# CH340G_VCC.net
KiCad netlist of a schematic drawn in Altium Designer
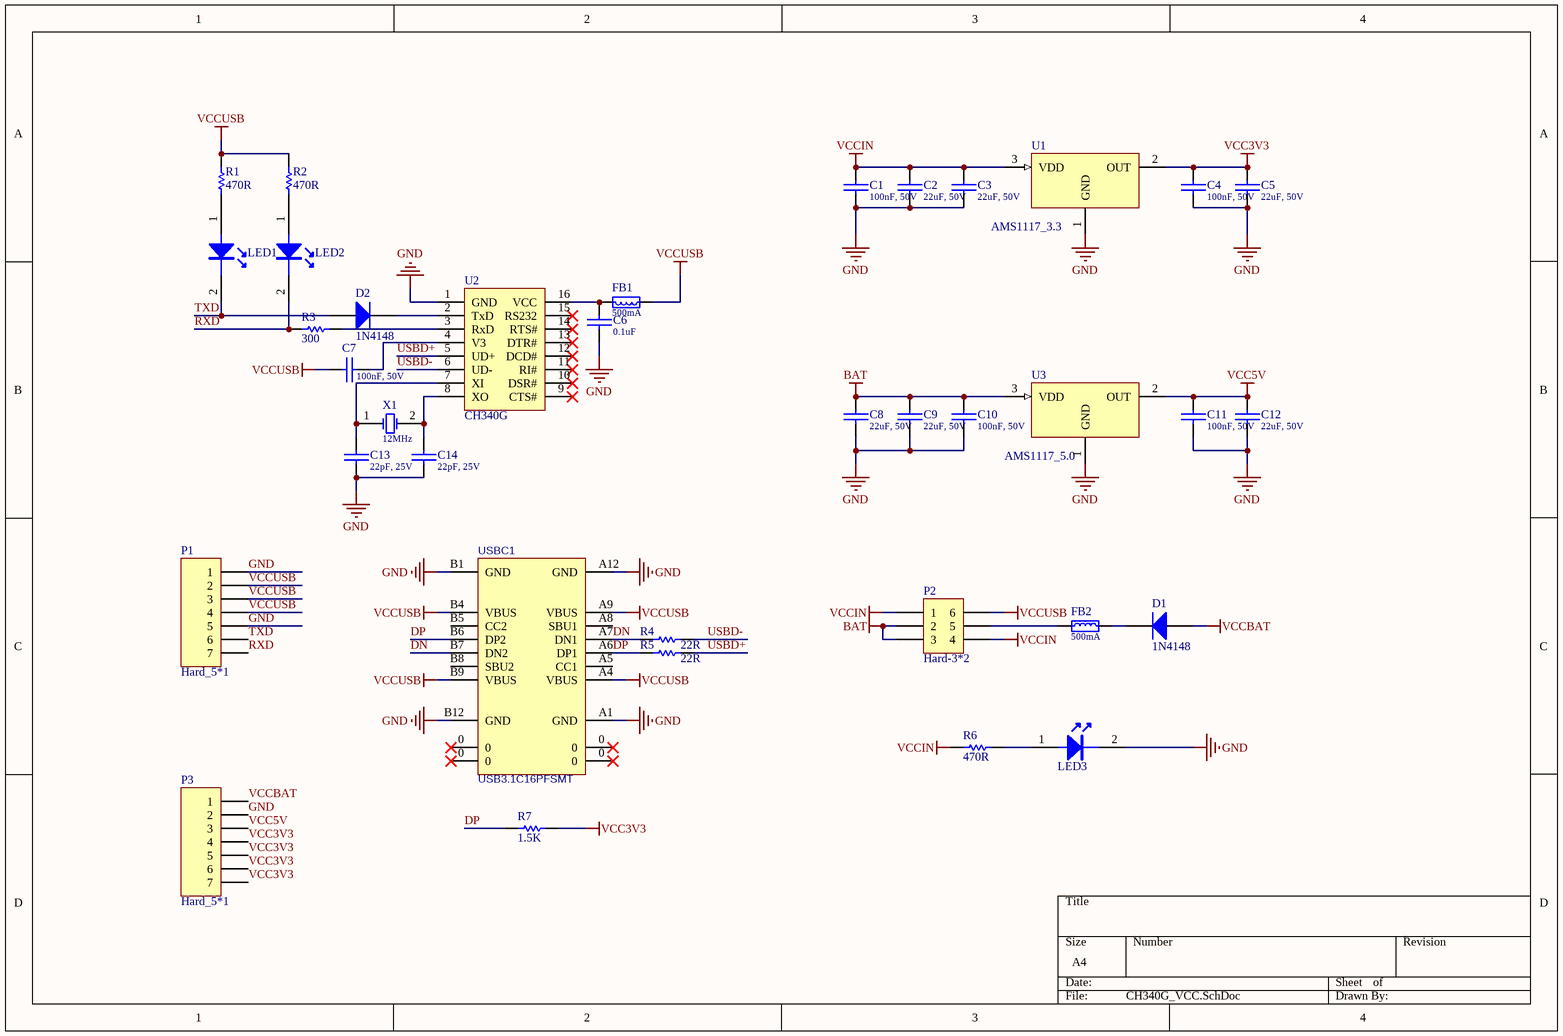
[diagram p0: CH340G_VCC.SchDoc]

(export (version "E")
  (design (tool "Eeschema 10.0.6"))
  (components
    (comp (ref "C1")
      (value "100nF, 50V")
      (footprint "C0603_QB")
      (description "Capacitor")
      (fields (field (name "MANUFACTURER") "国巨") (field (name "PARTNO") "11002050002"))
      (libsource (lib "Schlib1") (part "CAP"))
    )
    (comp (ref "C2")
      (value "22uF, 50V")
      (footprint "C0805_1.25mm_QB")
      (description "Capacitor")
      (fields (field (name "MANUFACTURER") "国巨") (field (name "PARTNO") "11002050002"))
      (libsource (lib "Schlib1") (part "CAP"))
    )
    (comp (ref "C3")
      (value "22uF, 50V")
      (footprint "C0805_1.25mm_QB")
      (description "Capacitor")
      (fields (field (name "MANUFACTURER") "国巨") (field (name "PARTNO") "11002050002"))
      (libsource (lib "Schlib1") (part "CAP"))
    )
    (comp (ref "C4")
      (value "100nF, 50V")
      (footprint "C0603_QB")
      (description "Capacitor")
      (fields (field (name "MANUFACTURER") "国巨") (field (name "PARTNO") "11002050002"))
      (libsource (lib "Schlib1") (part "CAP"))
    )
    (comp (ref "C5")
      (value "22uF, 50V")
      (footprint "C0805_1.25mm_QB")
      (description "Capacitor")
      (fields (field (name "MANUFACTURER") "国巨") (field (name "PARTNO") "11002050002"))
      (libsource (lib "Schlib1") (part "CAP"))
    )
    (comp (ref "C6")
      (value "0.1uF")
      (footprint "C0603_QB")
      (description "Capacitor")
      (fields (field (name "MANUFACTURER") "国巨") (field (name "PARTNO") "11002050002"))
      (libsource (lib "Schlib1") (part "CAP"))
    )
    (comp (ref "C7")
      (value "100nF, 50V")
      (footprint "C0603_QB")
      (description "Capacitor")
      (fields (field (name "MANUFACTURER") "国巨") (field (name "PARTNO") "11002050002"))
      (libsource (lib "Schlib1") (part "CAP"))
    )
    (comp (ref "C8")
      (value "22uF, 50V")
      (footprint "C0805_1.25mm_QB")
      (description "Capacitor")
      (fields (field (name "MANUFACTURER") "国巨") (field (name "PARTNO") "11002050002"))
      (libsource (lib "Schlib1") (part "CAP"))
    )
    (comp (ref "C9")
      (value "22uF, 50V")
      (footprint "C0805_1.25mm_QB")
      (description "Capacitor")
      (fields (field (name "MANUFACTURER") "国巨") (field (name "PARTNO") "11002050002"))
      (libsource (lib "Schlib1") (part "CAP"))
    )
    (comp (ref "C10")
      (value "100nF, 50V")
      (footprint "C0603_QB")
      (description "Capacitor")
      (fields (field (name "MANUFACTURER") "国巨") (field (name "PARTNO") "11002050002"))
      (libsource (lib "Schlib1") (part "CAP"))
    )
    (comp (ref "C11")
      (value "100nF, 50V")
      (footprint "C0603_QB")
      (description "Capacitor")
      (fields (field (name "MANUFACTURER") "国巨") (field (name "PARTNO") "11002050002"))
      (libsource (lib "Schlib1") (part "CAP"))
    )
    (comp (ref "C12")
      (value "22uF, 50V")
      (footprint "C0805_1.25mm_QB")
      (description "Capacitor")
      (fields (field (name "MANUFACTURER") "国巨") (field (name "PARTNO") "11002050002"))
      (libsource (lib "Schlib1") (part "CAP"))
    )
    (comp (ref "C13")
      (value "22pF, 25V")
      (footprint "C0603_QB")
      (description "Capacitor")
      (fields (field (name "MANUFACTURER") "国巨") (field (name "PARTNO") "11002050002"))
      (libsource (lib "Schlib1") (part "CAP"))
    )
    (comp (ref "C14")
      (value "22pF, 25V")
      (footprint "C0603_QB")
      (description "Capacitor")
      (fields (field (name "MANUFACTURER") "国巨") (field (name "PARTNO") "11002050002"))
      (libsource (lib "Schlib1") (part "CAP"))
    )
    (comp (ref "D1") (value "1N4148") (footprint "SOD_523_QB") (libsource (lib "Schlib1") (part "diode")))
    (comp (ref "D2") (value "1N4148") (footprint "SOD_523_QB") (libsource (lib "Schlib1") (part "diode")))
    (comp (ref "FB1")
      (value "500mA")
      (footprint "FB0603_QB")
      (description "Inductor")
      (fields (field (name "MANUFACTURER") "HOLDER") (field (name "Comment") "CBG160808U182"))
      (libsource (lib "Schlib1") (part "FB"))
    )
    (comp (ref "FB2")
      (value "500mA")
      (footprint "FB0603_QB")
      (description "Inductor")
      (fields (field (name "MANUFACTURER") "HOLDER") (field (name "Comment") "CBG160808U182"))
      (libsource (lib "Schlib1") (part "FB"))
    )
    (comp (ref "LED1")
      (value "19-217/R6C-AL1M2VY/3T")
      (footprint "LED_SMT_QB")
      (fields (field (name "MANUFACTURER") "亿光") (field (name "PARTNO") "11004030004"))
      (libsource (lib "Schlib1") (part "LED"))
    )
    (comp (ref "LED2")
      (value "19-217/R6C-AL1M2VY/3T")
      (footprint "LED_SMT_QB")
      (fields (field (name "MANUFACTURER") "亿光") (field (name "PARTNO") "11004030004"))
      (libsource (lib "Schlib1") (part "LED"))
    )
    (comp (ref "LED3")
      (value "19-217/R6C-AL1M2VY/3T")
      (footprint "LED_SMT_QB")
      (fields (field (name "MANUFACTURER") "亿光") (field (name "PARTNO") "11004030004"))
      (libsource (lib "Schlib1") (part "LED"))
    )
    (comp (ref "P1")
      (value "Hard_5*1")
      (footprint "HDR2.54-LI-4P")
      (libsource (lib "CH340G_VCC") (part "Hard_5*1"))
    )
    (comp (ref "P2")
      (value "Hard-3*2")
      (footprint "HDR2.54-LI-2x3P")
      (libsource (lib "Schlib1") (part "Hard-3*2"))
    )
    (comp (ref "P3")
      (value "Hard_5*1")
      (footprint "HDR2.54-LI-4P")
      (libsource (lib "CH340G_VCC") (part "Hard_5*1"))
    )
    (comp (ref "R1")
      (value "470R")
      (footprint "R0603_QB")
      (description "Resistor")
      (fields (field (name "MANUFACTURER") "国巨") (field (name "PARTNO") "11003020066"))
      (libsource (lib "Schlib1") (part "Res1"))
    )
    (comp (ref "R2")
      (value "470R")
      (footprint "R0603_QB")
      (description "Resistor")
      (fields (field (name "MANUFACTURER") "国巨") (field (name "PARTNO") "11003020066"))
      (libsource (lib "Schlib1") (part "Res1"))
    )
    (comp (ref "R3")
      (value "300")
      (footprint "R0603_QB")
      (description "Resistor")
      (fields (field (name "MANUFACTURER") "国巨") (field (name "PARTNO") "11003020066"))
      (libsource (lib "Schlib1") (part "Res1"))
    )
    (comp (ref "R4")
      (value "22R")
      (footprint "C0603_QB")
      (description "Resistor")
      (fields (field (name "MANUFACTURER") "国巨") (field (name "PARTNO") "11003020066"))
      (libsource (lib "Schlib1") (part "Res1"))
    )
    (comp (ref "R5")
      (value "22R")
      (footprint "C0603_QB")
      (description "Resistor")
      (fields (field (name "MANUFACTURER") "国巨") (field (name "PARTNO") "11003020066"))
      (libsource (lib "Schlib1") (part "Res1"))
    )
    (comp (ref "R6")
      (value "470R")
      (footprint "R0603_QB")
      (description "Resistor")
      (fields (field (name "MANUFACTURER") "国巨") (field (name "PARTNO") "11003020066"))
      (libsource (lib "Schlib1") (part "Res1"))
    )
    (comp (ref "R7")
      (value "1.5K")
      (footprint "R0603_QB")
      (description "Resistor")
      (fields (field (name "MANUFACTURER") "国巨") (field (name "PARTNO") "11003020066"))
      (libsource (lib "Schlib1") (part "Res1"))
    )
    (comp (ref "U1")
      (value "AMS1117_3.3")
      (footprint "SOT_89_QB")
      (description "LDO")
      (fields (field (name "MANUFACTURER") "明达微") (field (name "PARTNO") "11001090038"))
      (libsource (lib "CH340G_VCC") (part "MD5333"))
    )
    (comp (ref "U2") (value "CH340G") (footprint "SOP16N_N") (libsource (lib "Schlib1") (part "CH340G")))
    (comp (ref "U3")
      (value "AMS1117_5.0")
      (footprint "SOT_89_QB")
      (description "LDO")
      (fields (field (name "MANUFACTURER") "明达微") (field (name "PARTNO") "11001090038"))
      (libsource (lib "CH340G_VCC") (part "MD5350"))
    )
    (comp (ref "USBC1")
      (value "USB3.1C16PFSMT")
      (footprint "TYPE-C-USB-17")
      (libsource (lib "Schlib1") (part "USB3.1C16PFSMT"))
    )
    (comp (ref "X1")
      (value "12MHz")
      (footprint "ESB3.68640F20M23_QB")
      (description "Crystal Oscillator")
      (fields (field (name "MANUFACTURER") "EPSON") (field (name "PARTNO") "11012040004"))
      (libsource (lib "Schlib1") (part "XTAL"))
    )
  )
  (nets
    (net (code "1") (name "/DN") (class "Default")
      (node (ref "R4") (pin "1") (pinfunction "1_1") (pintype "passive"))
      (node (ref "USBC1") (pin "A7") (pinfunction "DN1_A7") (pintype "passive"))
      (node (ref "USBC1") (pin "B7") (pinfunction "DN2_B7") (pintype "passive"))
    )
    (net (code "2") (name "/DP") (class "Default")
      (node (ref "R5") (pin "1") (pinfunction "1_1") (pintype "passive"))
      (node (ref "R7") (pin "1") (pinfunction "1_1") (pintype "passive"))
      (node (ref "USBC1") (pin "A6") (pinfunction "DP1_A6") (pintype "passive"))
      (node (ref "USBC1") (pin "B6") (pinfunction "DP2_B6") (pintype "passive"))
    )
    (net (code "3") (name "/RXD") (class "Default")
      (node (ref "LED2") (pin "2") (pinfunction "K_2") (pintype "passive"))
      (node (ref "P1") (pin "7") (pinfunction "7_7") (pintype "passive"))
      (node (ref "R3") (pin "1") (pinfunction "1_1") (pintype "passive"))
    )
    (net (code "4") (name "/TXD") (class "Default")
      (node (ref "D2") (pin "1") (pinfunction "A_1") (pintype "passive"))
      (node (ref "LED1") (pin "2") (pinfunction "K_2") (pintype "passive"))
      (node (ref "P1") (pin "6") (pinfunction "6_6") (pintype "passive"))
    )
    (net (code "5") (name "/USBD+") (class "Default")
      (node (ref "R5") (pin "2") (pinfunction "2_2") (pintype "passive"))
      (node (ref "U2") (pin "5") (pinfunction "UD+_5") (pintype "passive"))
    )
    (net (code "6") (name "/USBD-") (class "Default")
      (node (ref "R4") (pin "2") (pinfunction "2_2") (pintype "passive"))
      (node (ref "U2") (pin "6") (pinfunction "UD-_6") (pintype "passive"))
    )
    (net (code "7") (name "BAT") (class "Default")
      (node (ref "C10") (pin "2") (pinfunction "2_2") (pintype "passive"))
      (node (ref "C8") (pin "2") (pinfunction "2_2") (pintype "passive"))
      (node (ref "C9") (pin "2") (pinfunction "2_2") (pintype "passive"))
      (node (ref "P2") (pin "2") (pinfunction "2_2") (pintype "passive"))
      (node (ref "P2") (pin "3") (pinfunction "3_3") (pintype "passive"))
      (node (ref "U3") (pin "3") (pinfunction "VDD_3") (pintype "input"))
    )
    (net (code "8") (name "GND") (class "Default")
      (node (ref "C1") (pin "1") (pinfunction "1_1") (pintype "passive"))
      (node (ref "C10") (pin "1") (pinfunction "1_1") (pintype "passive"))
      (node (ref "C11") (pin "1") (pinfunction "1_1") (pintype "passive"))
      (node (ref "C12") (pin "1") (pinfunction "1_1") (pintype "passive"))
      (node (ref "C13") (pin "1") (pinfunction "1_1") (pintype "passive"))
      (node (ref "C14") (pin "1") (pinfunction "1_1") (pintype "passive"))
      (node (ref "C2") (pin "1") (pinfunction "1_1") (pintype "passive"))
      (node (ref "C3") (pin "1") (pinfunction "1_1") (pintype "passive"))
      (node (ref "C4") (pin "1") (pinfunction "1_1") (pintype "passive"))
      (node (ref "C5") (pin "1") (pinfunction "1_1") (pintype "passive"))
      (node (ref "C6") (pin "1") (pinfunction "1_1") (pintype "passive"))
      (node (ref "C8") (pin "1") (pinfunction "1_1") (pintype "passive"))
      (node (ref "C9") (pin "1") (pinfunction "1_1") (pintype "passive"))
      (node (ref "LED3") (pin "2") (pinfunction "K_2") (pintype "passive"))
      (node (ref "P1") (pin "1") (pinfunction "1_1") (pintype "passive"))
      (node (ref "P1") (pin "5") (pinfunction "5_5") (pintype "passive"))
      (node (ref "P3") (pin "2") (pinfunction "2_2") (pintype "passive"))
      (node (ref "U1") (pin "1") (pinfunction "GND_1") (pintype "passive"))
      (node (ref "U2") (pin "1") (pinfunction "GND_1") (pintype "passive"))
      (node (ref "U3") (pin "1") (pinfunction "GND_1") (pintype "passive"))
      (node (ref "USBC1") (pin "A1") (pinfunction "GND_A1") (pintype "passive"))
      (node (ref "USBC1") (pin "A12") (pinfunction "GND_A12") (pintype "passive"))
      (node (ref "USBC1") (pin "B1") (pinfunction "GND_B1") (pintype "passive"))
      (node (ref "USBC1") (pin "B12") (pinfunction "GND_B12") (pintype "passive"))
    )
    (net (code "9") (name "Net-(D1-K)") (class "Default")
      (node (ref "D1") (pin "2") (pinfunction "K_2") (pintype "passive"))
      (node (ref "FB2") (pin "2") (pinfunction "2_2") (pintype "passive"))
    )
    (net (code "10") (name "Net-(D2-K)") (class "Default")
      (node (ref "D2") (pin "2") (pinfunction "K_2") (pintype "passive"))
      (node (ref "U2") (pin "2") (pinfunction "TxD_2") (pintype "passive"))
    )
    (net (code "11") (name "Net-(FB2-Pad1)") (class "Default")
      (node (ref "FB2") (pin "1") (pinfunction "1_1") (pintype "passive"))
      (node (ref "P2") (pin "5") (pinfunction "5_5") (pintype "passive"))
    )
    (net (code "12") (name "Net-(LED1-A)") (class "Default")
      (node (ref "LED1") (pin "1") (pinfunction "A_1") (pintype "passive"))
      (node (ref "R1") (pin "1") (pinfunction "1_1") (pintype "passive"))
    )
    (net (code "13") (name "Net-(LED2-A)") (class "Default")
      (node (ref "LED2") (pin "1") (pinfunction "A_1") (pintype "passive"))
      (node (ref "R2") (pin "1") (pinfunction "1_1") (pintype "passive"))
    )
    (net (code "14") (name "Net-(LED3-A)") (class "Default")
      (node (ref "LED3") (pin "1") (pinfunction "A_1") (pintype "passive"))
      (node (ref "R6") (pin "2") (pinfunction "2_2") (pintype "passive"))
    )
    (net (code "15") (name "Net-(U2-RxD)") (class "Default")
      (node (ref "R3") (pin "2") (pinfunction "2_2") (pintype "passive"))
      (node (ref "U2") (pin "3") (pinfunction "RxD_3") (pintype "passive"))
    )
    (net (code "16") (name "Net-(U2-V3)") (class "Default")
      (node (ref "C7") (pin "2") (pinfunction "2_2") (pintype "passive"))
      (node (ref "U2") (pin "4") (pinfunction "V3_4") (pintype "passive"))
    )
    (net (code "17") (name "Net-(U2-VCC)") (class "Default")
      (node (ref "C6") (pin "2") (pinfunction "2_2") (pintype "passive"))
      (node (ref "FB1") (pin "2") (pinfunction "2_2") (pintype "passive"))
      (node (ref "U2") (pin "16") (pinfunction "VCC_16") (pintype "passive"))
    )
    (net (code "18") (name "Net-(U2-XI)") (class "Default")
      (node (ref "C13") (pin "2") (pinfunction "2_2") (pintype "passive"))
      (node (ref "U2") (pin "7") (pinfunction "XI_7") (pintype "passive"))
      (node (ref "X1") (pin "1") (pinfunction "OSC1_1") (pintype "passive"))
    )
    (net (code "19") (name "Net-(U2-XO)") (class "Default")
      (node (ref "C14") (pin "2") (pinfunction "2_2") (pintype "passive"))
      (node (ref "U2") (pin "8") (pinfunction "XO_8") (pintype "passive"))
      (node (ref "X1") (pin "2") (pinfunction "OSC2_2") (pintype "passive"))
    )
    (net (code "20") (name "VCC3V3") (class "Default")
      (node (ref "C4") (pin "2") (pinfunction "2_2") (pintype "passive"))
      (node (ref "C5") (pin "2") (pinfunction "2_2") (pintype "passive"))
      (node (ref "P3") (pin "4") (pinfunction "4_4") (pintype "passive"))
      (node (ref "P3") (pin "5") (pinfunction "5_5") (pintype "passive"))
      (node (ref "P3") (pin "6") (pinfunction "6_6") (pintype "passive"))
      (node (ref "P3") (pin "7") (pinfunction "7_7") (pintype "passive"))
      (node (ref "R7") (pin "2") (pinfunction "2_2") (pintype "passive"))
      (node (ref "U1") (pin "2") (pinfunction "OUT_2") (pintype "power_in"))
    )
    (net (code "21") (name "VCC5V") (class "Default")
      (node (ref "C11") (pin "2") (pinfunction "2_2") (pintype "passive"))
      (node (ref "C12") (pin "2") (pinfunction "2_2") (pintype "passive"))
      (node (ref "P3") (pin "3") (pinfunction "3_3") (pintype "passive"))
      (node (ref "U3") (pin "2") (pinfunction "OUT_2") (pintype "power_in"))
    )
    (net (code "22") (name "VCCBAT") (class "Default")
      (node (ref "D1") (pin "1") (pinfunction "A_1") (pintype "passive"))
      (node (ref "P3") (pin "1") (pinfunction "1_1") (pintype "passive"))
    )
    (net (code "23") (name "VCCIN") (class "Default")
      (node (ref "C1") (pin "2") (pinfunction "2_2") (pintype "passive"))
      (node (ref "C2") (pin "2") (pinfunction "2_2") (pintype "passive"))
      (node (ref "C3") (pin "2") (pinfunction "2_2") (pintype "passive"))
      (node (ref "P2") (pin "1") (pinfunction "1_1") (pintype "passive"))
      (node (ref "P2") (pin "4") (pinfunction "4_4") (pintype "passive"))
      (node (ref "R6") (pin "1") (pinfunction "1_1") (pintype "passive"))
      (node (ref "U1") (pin "3") (pinfunction "VDD_3") (pintype "input"))
    )
    (net (code "24") (name "VCCUSB") (class "Default")
      (node (ref "C7") (pin "1") (pinfunction "1_1") (pintype "passive"))
      (node (ref "FB1") (pin "1") (pinfunction "1_1") (pintype "passive"))
      (node (ref "P1") (pin "2") (pinfunction "2_2") (pintype "passive"))
      (node (ref "P1") (pin "3") (pinfunction "3_3") (pintype "passive"))
      (node (ref "P1") (pin "4") (pinfunction "4_4") (pintype "passive"))
      (node (ref "P2") (pin "6") (pinfunction "6_6") (pintype "passive"))
      (node (ref "R1") (pin "2") (pinfunction "2_2") (pintype "passive"))
      (node (ref "R2") (pin "2") (pinfunction "2_2") (pintype "passive"))
      (node (ref "USBC1") (pin "A4") (pinfunction "VBUS_A4") (pintype "passive"))
      (node (ref "USBC1") (pin "A9") (pinfunction "VBUS_A9") (pintype "passive"))
      (node (ref "USBC1") (pin "B4") (pinfunction "VBUS_B4") (pintype "passive"))
      (node (ref "USBC1") (pin "B9") (pinfunction "VBUS_B9") (pintype "passive"))
    )
    (net (code "25") (name "unconnected-(U2-CTS#-Pad9)") (class "Default")
      (node (ref "U2") (pin "9") (pinfunction "CTS#_9") (pintype "passive+no_connect"))
    )
    (net (code "26") (name "unconnected-(U2-DCD#-Pad12)") (class "Default")
      (node (ref "U2") (pin "12") (pinfunction "DCD#_12") (pintype "passive+no_connect"))
    )
    (net (code "27") (name "unconnected-(U2-DSR#-Pad10)") (class "Default")
      (node (ref "U2") (pin "10") (pinfunction "DSR#_10") (pintype "passive+no_connect"))
    )
    (net (code "28") (name "unconnected-(U2-DTR#-Pad13)") (class "Default")
      (node (ref "U2") (pin "13") (pinfunction "DTR#_13") (pintype "passive+no_connect"))
    )
    (net (code "29") (name "unconnected-(U2-RI#-Pad11)") (class "Default")
      (node (ref "U2") (pin "11") (pinfunction "RI#_11") (pintype "passive+no_connect"))
    )
    (net (code "30") (name "unconnected-(U2-RS232-Pad15)") (class "Default")
      (node (ref "U2") (pin "15") (pinfunction "RS232_15") (pintype "passive+no_connect"))
    )
    (net (code "31") (name "unconnected-(U2-RTS#-Pad14)") (class "Default")
      (node (ref "U2") (pin "14") (pinfunction "RTS#_14") (pintype "passive+no_connect"))
    )
    (net (code "32") (name "unconnected-(USBC1-CC1-PadA5)") (class "Default")
      (node (ref "USBC1") (pin "A5") (pinfunction "CC1_A5") (pintype "passive"))
    )
    (net (code "33") (name "unconnected-(USBC1-CC2-PadB5)") (class "Default")
      (node (ref "USBC1") (pin "B5") (pinfunction "CC2_B5") (pintype "passive"))
    )
    (net (code "34") (name "unconnected-(USBC1-Pad0)") (class "Default")
      (node (ref "USBC1") (pin "0") (pinfunction "0_0") (pintype "passive+no_connect"))
    )
    (net (code "35") (name "unconnected-(USBC1-Pad0)_1") (class "Default")
      (node (ref "USBC1") (pin "0") (pinfunction "0_0") (pintype "passive+no_connect"))
    )
    (net (code "36") (name "unconnected-(USBC1-Pad0)_2") (class "Default")
      (node (ref "USBC1") (pin "0") (pinfunction "0_0") (pintype "passive+no_connect"))
    )
    (net (code "37") (name "unconnected-(USBC1-Pad0)_3") (class "Default")
      (node (ref "USBC1") (pin "0") (pinfunction "0_0") (pintype "passive+no_connect"))
    )
    (net (code "38") (name "unconnected-(USBC1-SBU1-PadA8)") (class "Default")
      (node (ref "USBC1") (pin "A8") (pinfunction "SBU1_A8") (pintype "passive"))
    )
    (net (code "39") (name "unconnected-(USBC1-SBU2-PadB8)") (class "Default")
      (node (ref "USBC1") (pin "B8") (pinfunction "SBU2_B8") (pintype "passive"))
    )
  )
)
